# TempController.net
KiCad netlist of a schematic drawn in Altium Designer
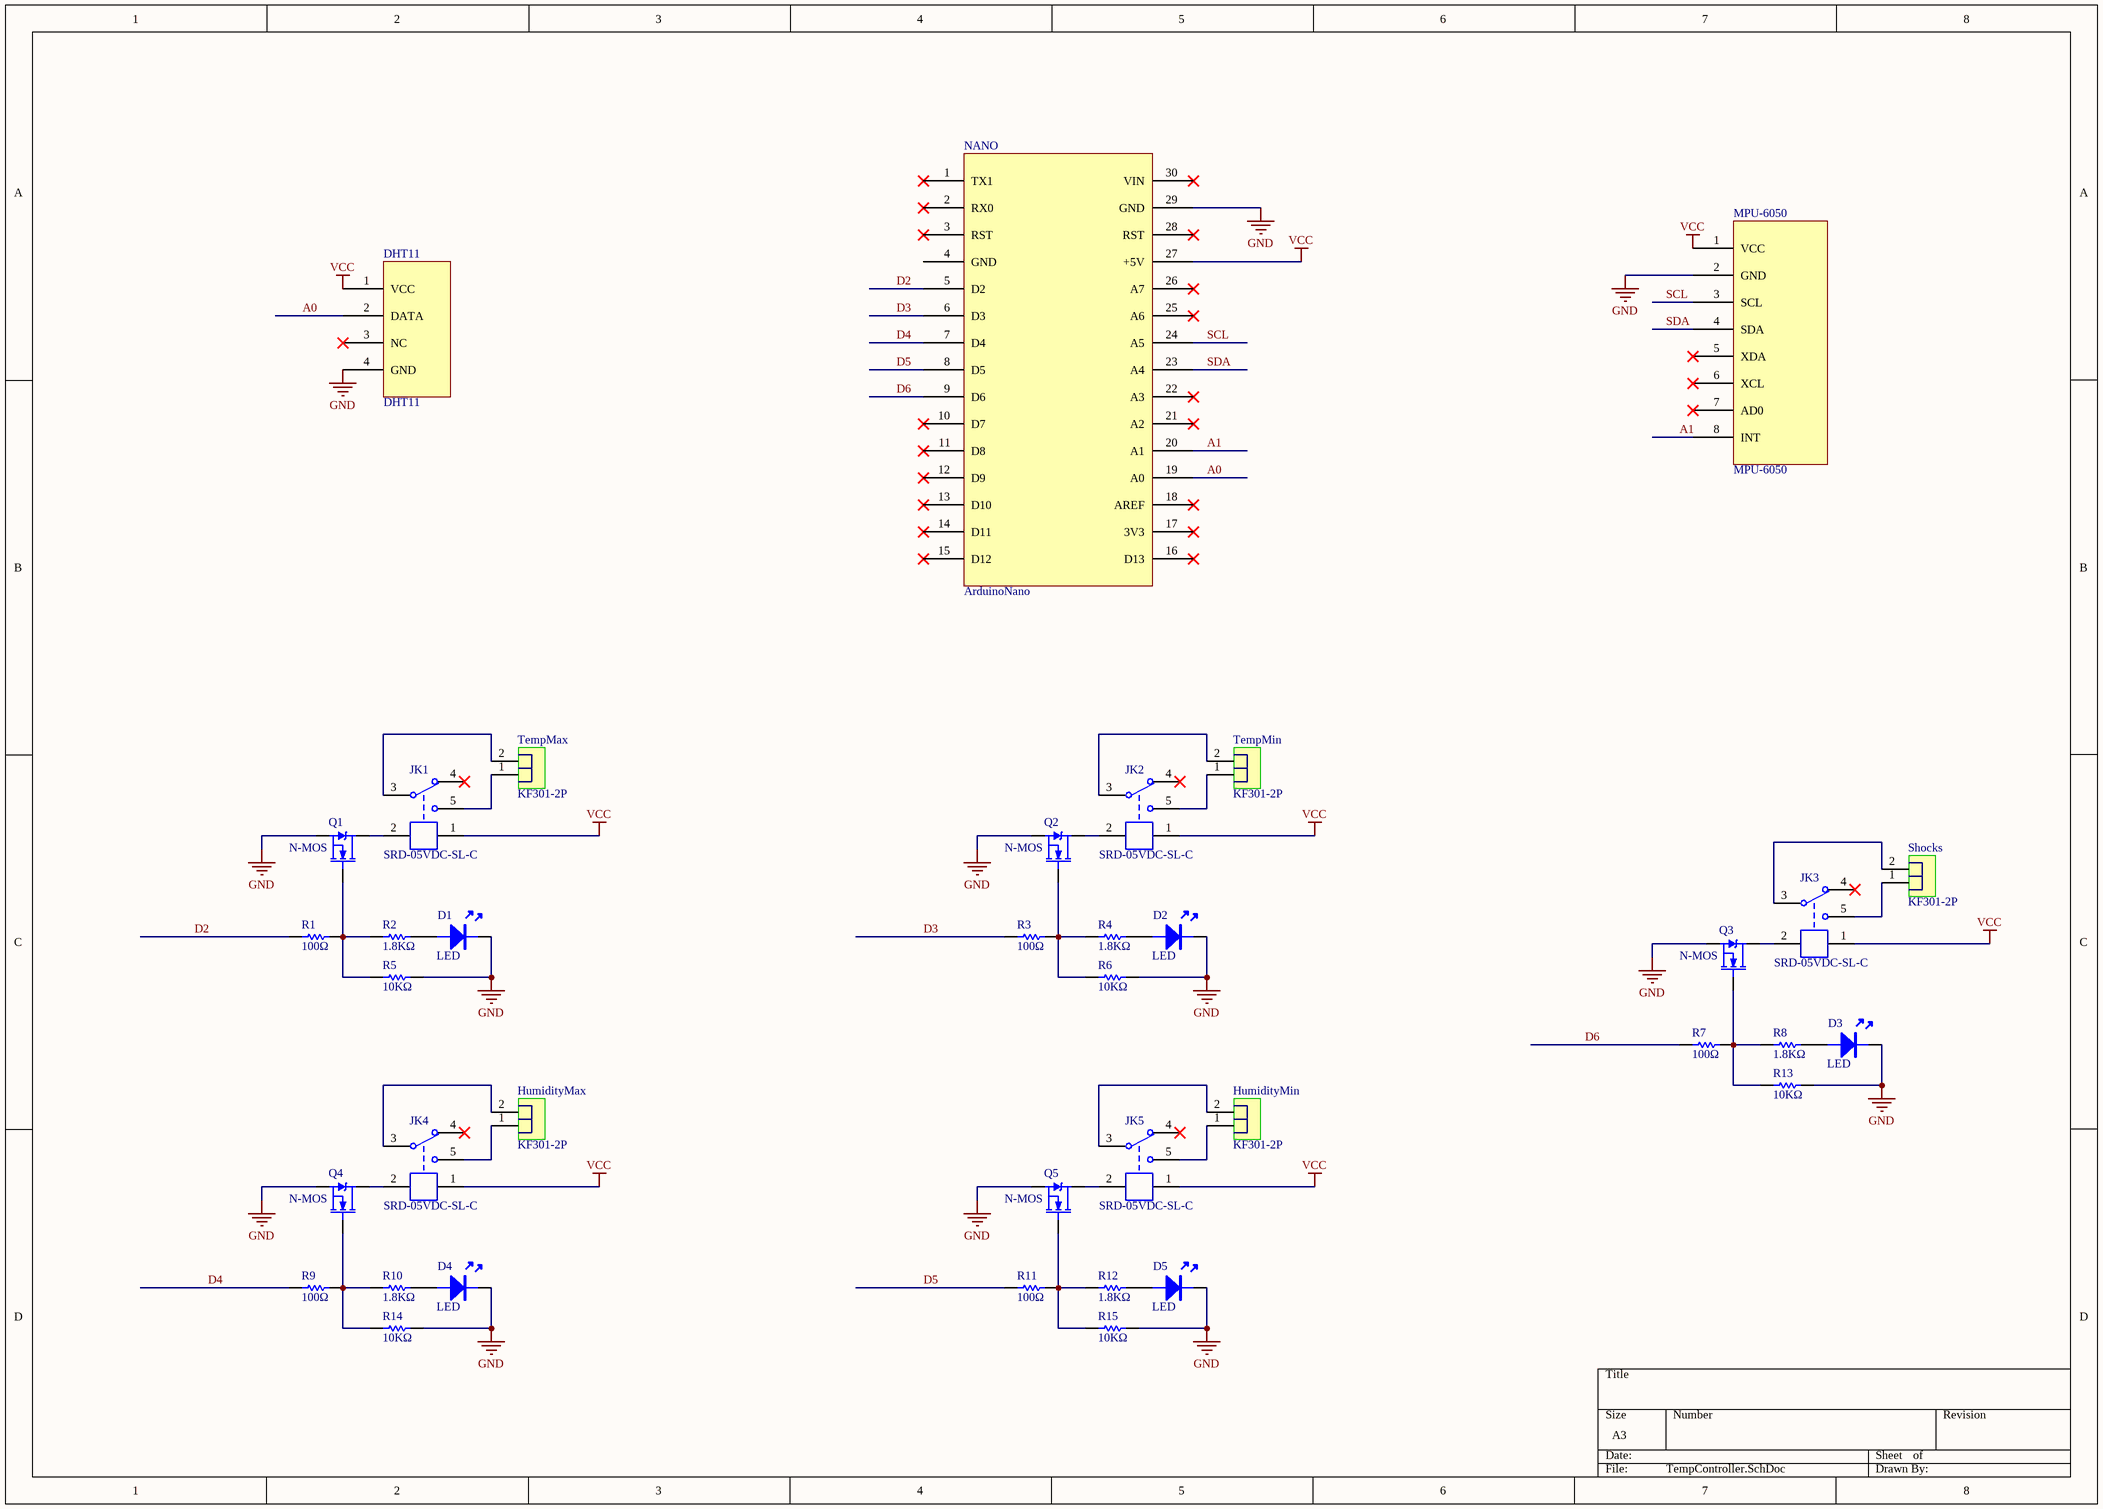
[diagram p0: TempController.SchDoc]

(export (version "E")
  (design (tool "Eeschema 10.0.6"))
  (components
    (comp (ref "D1") (value "LED") (footprint "LED-0805Y") (libsource (lib "LED") (part "LED")))
    (comp (ref "D2") (value "LED") (footprint "LED-0805Y") (libsource (lib "LED") (part "LED")))
    (comp (ref "D3") (value "LED") (footprint "LED-0805Y") (libsource (lib "LED") (part "LED")))
    (comp (ref "D4") (value "LED") (footprint "LED-0805Y") (libsource (lib "LED") (part "LED")))
    (comp (ref "D5") (value "LED") (footprint "LED-0805Y") (libsource (lib "LED") (part "LED")))
    (comp (ref "DHT11") (value "DHT11") (footprint "DHT11") (libsource (lib "TempController") (part "DHT11")))
    (comp (ref "HumidityMax")
      (value "KF301-2P")
      (footprint "KF128-3.81-2P")
      (libsource (lib "KF128") (part "KF128-2P"))
    )
    (comp (ref "HumidityMin")
      (value "KF301-2P")
      (footprint "KF128-3.81-2P")
      (libsource (lib "KF128") (part "KF128-2P"))
    )
    (comp (ref "JK1")
      (value "SRD-05VDC-SL-C")
      (footprint "SRD-C_B")
      (description "5V一组转换")
      (libsource (lib "继电器") (part "SRD-05VDC-SL-C"))
    )
    (comp (ref "JK2")
      (value "SRD-05VDC-SL-C")
      (footprint "SRD-C_B")
      (description "5V一组转换")
      (libsource (lib "继电器") (part "SRD-05VDC-SL-C"))
    )
    (comp (ref "JK3")
      (value "SRD-05VDC-SL-C")
      (footprint "SRD-C_B")
      (description "5V一组转换")
      (libsource (lib "继电器") (part "SRD-05VDC-SL-C"))
    )
    (comp (ref "JK4")
      (value "SRD-05VDC-SL-C")
      (footprint "SRD-C_B")
      (description "5V一组转换")
      (libsource (lib "继电器") (part "SRD-05VDC-SL-C"))
    )
    (comp (ref "JK5")
      (value "SRD-05VDC-SL-C")
      (footprint "SRD-C_B")
      (description "5V一组转换")
      (libsource (lib "继电器") (part "SRD-05VDC-SL-C"))
    )
    (comp (ref "MPU-6050")
      (value "MPU-6050")
      (footprint "MPU-6050")
      (libsource (lib "TempController") (part "MPU-6050"))
    )
    (comp (ref "NANO")
      (value "ArduinoNano")
      (footprint "ArduinoNano")
      (libsource (lib "TempController") (part "ArduinoNano"))
    )
    (comp (ref "Q1")
      (value "N-MOS")
      (footprint "TO252")
      (description "N沟道场效应管")
      (libsource (lib "MOS管") (part "N-MOS"))
    )
    (comp (ref "Q2")
      (value "N-MOS")
      (footprint "TO252")
      (description "N沟道场效应管")
      (libsource (lib "MOS管") (part "N-MOS"))
    )
    (comp (ref "Q3")
      (value "N-MOS")
      (footprint "TO252")
      (description "N沟道场效应管")
      (libsource (lib "MOS管") (part "N-MOS"))
    )
    (comp (ref "Q4")
      (value "N-MOS")
      (footprint "TO252")
      (description "N沟道场效应管")
      (libsource (lib "MOS管") (part "N-MOS"))
    )
    (comp (ref "Q5")
      (value "N-MOS")
      (footprint "TO252")
      (description "N沟道场效应管")
      (libsource (lib "MOS管") (part "N-MOS"))
    )
    (comp (ref "R1") (value "100Ω") (footprint "0805R") (libsource (lib "电阻") (part "RES")))
    (comp (ref "R2") (value "1.8KΩ") (footprint "0805R") (libsource (lib "电阻") (part "RES")))
    (comp (ref "R3") (value "100Ω") (footprint "0805R") (libsource (lib "电阻") (part "RES")))
    (comp (ref "R4") (value "1.8KΩ") (footprint "0805R") (libsource (lib "电阻") (part "RES")))
    (comp (ref "R5") (value "10KΩ") (footprint "0805R") (libsource (lib "电阻") (part "RES")))
    (comp (ref "R6") (value "10KΩ") (footprint "0805R") (libsource (lib "电阻") (part "RES")))
    (comp (ref "R7") (value "100Ω") (footprint "0805R") (libsource (lib "电阻") (part "RES")))
    (comp (ref "R8") (value "1.8KΩ") (footprint "0805R") (libsource (lib "电阻") (part "RES")))
    (comp (ref "R9") (value "100Ω") (footprint "0805R") (libsource (lib "电阻") (part "RES")))
    (comp (ref "R10") (value "1.8KΩ") (footprint "0805R") (libsource (lib "电阻") (part "RES")))
    (comp (ref "R11") (value "100Ω") (footprint "0805R") (libsource (lib "电阻") (part "RES")))
    (comp (ref "R12") (value "1.8KΩ") (footprint "0805R") (libsource (lib "电阻") (part "RES")))
    (comp (ref "R13") (value "10KΩ") (footprint "0805R") (libsource (lib "电阻") (part "RES")))
    (comp (ref "R14") (value "10KΩ") (footprint "0805R") (libsource (lib "电阻") (part "RES")))
    (comp (ref "R15") (value "10KΩ") (footprint "0805R") (libsource (lib "电阻") (part "RES")))
    (comp (ref "Shocks")
      (value "KF301-2P")
      (footprint "KF128-3.81-2P")
      (libsource (lib "KF128") (part "KF128-2P"))
    )
    (comp (ref "TempMax")
      (value "KF301-2P")
      (footprint "KF128-3.81-2P")
      (libsource (lib "KF128") (part "KF128-2P"))
    )
    (comp (ref "TempMin")
      (value "KF301-2P")
      (footprint "KF128-3.81-2P")
      (libsource (lib "KF128") (part "KF128-2P"))
    )
  )
  (nets
    (net (code "1") (name "/A0") (class "Default")
      (node (ref "DHT11") (pin "2") (pinfunction "DATA_2") (pintype "passive"))
      (node (ref "NANO") (pin "19") (pinfunction "A0_19") (pintype "passive"))
    )
    (net (code "2") (name "/A1") (class "Default")
      (node (ref "MPU-6050") (pin "8") (pinfunction "INT_8") (pintype "passive"))
      (node (ref "NANO") (pin "20") (pinfunction "A1_20") (pintype "passive"))
    )
    (net (code "3") (name "/D2") (class "Default")
      (node (ref "NANO") (pin "5") (pinfunction "D2_5") (pintype "passive"))
      (node (ref "R1") (pin "1") (pinfunction "1_1") (pintype "passive"))
    )
    (net (code "4") (name "/D3") (class "Default")
      (node (ref "NANO") (pin "6") (pinfunction "D3_6") (pintype "passive"))
      (node (ref "R3") (pin "1") (pinfunction "1_1") (pintype "passive"))
    )
    (net (code "5") (name "/D4") (class "Default")
      (node (ref "NANO") (pin "7") (pinfunction "D4_7") (pintype "passive"))
      (node (ref "R9") (pin "1") (pinfunction "1_1") (pintype "passive"))
    )
    (net (code "6") (name "/D5") (class "Default")
      (node (ref "NANO") (pin "8") (pinfunction "D5_8") (pintype "passive"))
      (node (ref "R11") (pin "1") (pinfunction "1_1") (pintype "passive"))
    )
    (net (code "7") (name "/D6") (class "Default")
      (node (ref "NANO") (pin "9") (pinfunction "D6_9") (pintype "passive"))
      (node (ref "R7") (pin "1") (pinfunction "1_1") (pintype "passive"))
    )
    (net (code "8") (name "/SCL") (class "Default")
      (node (ref "MPU-6050") (pin "3") (pinfunction "SCL_3") (pintype "passive"))
      (node (ref "NANO") (pin "24") (pinfunction "A5_24") (pintype "passive"))
    )
    (net (code "9") (name "/SDA") (class "Default")
      (node (ref "MPU-6050") (pin "4") (pinfunction "SDA_4") (pintype "passive"))
      (node (ref "NANO") (pin "23") (pinfunction "A4_23") (pintype "passive"))
    )
    (net (code "10") (name "GND") (class "Default")
      (node (ref "D1") (pin "K") (pinfunction "K_K") (pintype "passive"))
      (node (ref "D2") (pin "K") (pinfunction "K_K") (pintype "passive"))
      (node (ref "D3") (pin "K") (pinfunction "K_K") (pintype "passive"))
      (node (ref "D4") (pin "K") (pinfunction "K_K") (pintype "passive"))
      (node (ref "D5") (pin "K") (pinfunction "K_K") (pintype "passive"))
      (node (ref "DHT11") (pin "4") (pinfunction "GND_4") (pintype "passive"))
      (node (ref "MPU-6050") (pin "2") (pinfunction "GND_2") (pintype "passive"))
      (node (ref "NANO") (pin "29") (pinfunction "GND_29") (pintype "passive"))
      (node (ref "Q1") (pin "S") (pinfunction "S_S") (pintype "passive"))
      (node (ref "Q2") (pin "S") (pinfunction "S_S") (pintype "passive"))
      (node (ref "Q3") (pin "S") (pinfunction "S_S") (pintype "passive"))
      (node (ref "Q4") (pin "S") (pinfunction "S_S") (pintype "passive"))
      (node (ref "Q5") (pin "S") (pinfunction "S_S") (pintype "passive"))
      (node (ref "R13") (pin "2") (pinfunction "2_2") (pintype "passive"))
      (node (ref "R14") (pin "2") (pinfunction "2_2") (pintype "passive"))
      (node (ref "R15") (pin "2") (pinfunction "2_2") (pintype "passive"))
      (node (ref "R5") (pin "2") (pinfunction "2_2") (pintype "passive"))
      (node (ref "R6") (pin "2") (pinfunction "2_2") (pintype "passive"))
    )
    (net (code "11") (name "Net-(D1-PadA)") (class "Default")
      (node (ref "D1") (pin "A") (pinfunction "A_A") (pintype "passive"))
      (node (ref "R2") (pin "2") (pinfunction "2_2") (pintype "passive"))
    )
    (net (code "12") (name "Net-(D2-PadA)") (class "Default")
      (node (ref "D2") (pin "A") (pinfunction "A_A") (pintype "passive"))
      (node (ref "R4") (pin "2") (pinfunction "2_2") (pintype "passive"))
    )
    (net (code "13") (name "Net-(D3-PadA)") (class "Default")
      (node (ref "D3") (pin "A") (pinfunction "A_A") (pintype "passive"))
      (node (ref "R8") (pin "2") (pinfunction "2_2") (pintype "passive"))
    )
    (net (code "14") (name "Net-(D4-PadA)") (class "Default")
      (node (ref "D4") (pin "A") (pinfunction "A_A") (pintype "passive"))
      (node (ref "R10") (pin "2") (pinfunction "2_2") (pintype "passive"))
    )
    (net (code "15") (name "Net-(D5-PadA)") (class "Default")
      (node (ref "D5") (pin "A") (pinfunction "A_A") (pintype "passive"))
      (node (ref "R12") (pin "2") (pinfunction "2_2") (pintype "passive"))
    )
    (net (code "16") (name "Net-(HumidityMax-Pad1)") (class "Default")
      (node (ref "HumidityMax") (pin "1") (pinfunction "1_1") (pintype "passive"))
      (node (ref "JK4") (pin "5") (pinfunction "5_5") (pintype "passive"))
    )
    (net (code "17") (name "Net-(HumidityMax-Pad2)") (class "Default")
      (node (ref "HumidityMax") (pin "2") (pinfunction "2_2") (pintype "passive"))
      (node (ref "JK4") (pin "3") (pinfunction "3_3") (pintype "passive"))
    )
    (net (code "18") (name "Net-(HumidityMin-Pad1)") (class "Default")
      (node (ref "HumidityMin") (pin "1") (pinfunction "1_1") (pintype "passive"))
      (node (ref "JK5") (pin "5") (pinfunction "5_5") (pintype "passive"))
    )
    (net (code "19") (name "Net-(HumidityMin-Pad2)") (class "Default")
      (node (ref "HumidityMin") (pin "2") (pinfunction "2_2") (pintype "passive"))
      (node (ref "JK5") (pin "3") (pinfunction "3_3") (pintype "passive"))
    )
    (net (code "20") (name "Net-(JK1-Pad2)") (class "Default")
      (node (ref "JK1") (pin "2") (pinfunction "2_2") (pintype "passive"))
      (node (ref "Q1") (pin "D") (pinfunction "D_D") (pintype "passive"))
    )
    (net (code "21") (name "Net-(JK1-Pad3)") (class "Default")
      (node (ref "JK1") (pin "3") (pinfunction "3_3") (pintype "passive"))
      (node (ref "TempMax") (pin "2") (pinfunction "2_2") (pintype "passive"))
    )
    (net (code "22") (name "Net-(JK1-Pad5)") (class "Default")
      (node (ref "JK1") (pin "5") (pinfunction "5_5") (pintype "passive"))
      (node (ref "TempMax") (pin "1") (pinfunction "1_1") (pintype "passive"))
    )
    (net (code "23") (name "Net-(JK2-Pad2)") (class "Default")
      (node (ref "JK2") (pin "2") (pinfunction "2_2") (pintype "passive"))
      (node (ref "Q2") (pin "D") (pinfunction "D_D") (pintype "passive"))
    )
    (net (code "24") (name "Net-(JK2-Pad3)") (class "Default")
      (node (ref "JK2") (pin "3") (pinfunction "3_3") (pintype "passive"))
      (node (ref "TempMin") (pin "2") (pinfunction "2_2") (pintype "passive"))
    )
    (net (code "25") (name "Net-(JK2-Pad5)") (class "Default")
      (node (ref "JK2") (pin "5") (pinfunction "5_5") (pintype "passive"))
      (node (ref "TempMin") (pin "1") (pinfunction "1_1") (pintype "passive"))
    )
    (net (code "26") (name "Net-(JK3-Pad2)") (class "Default")
      (node (ref "JK3") (pin "2") (pinfunction "2_2") (pintype "passive"))
      (node (ref "Q3") (pin "D") (pinfunction "D_D") (pintype "passive"))
    )
    (net (code "27") (name "Net-(JK3-Pad3)") (class "Default")
      (node (ref "JK3") (pin "3") (pinfunction "3_3") (pintype "passive"))
      (node (ref "Shocks") (pin "2") (pinfunction "2_2") (pintype "passive"))
    )
    (net (code "28") (name "Net-(JK3-Pad5)") (class "Default")
      (node (ref "JK3") (pin "5") (pinfunction "5_5") (pintype "passive"))
      (node (ref "Shocks") (pin "1") (pinfunction "1_1") (pintype "passive"))
    )
    (net (code "29") (name "Net-(JK4-Pad2)") (class "Default")
      (node (ref "JK4") (pin "2") (pinfunction "2_2") (pintype "passive"))
      (node (ref "Q4") (pin "D") (pinfunction "D_D") (pintype "passive"))
    )
    (net (code "30") (name "Net-(JK5-Pad2)") (class "Default")
      (node (ref "JK5") (pin "2") (pinfunction "2_2") (pintype "passive"))
      (node (ref "Q5") (pin "D") (pinfunction "D_D") (pintype "passive"))
    )
    (net (code "31") (name "Net-(Q1-PadG)") (class "Default")
      (node (ref "Q1") (pin "G") (pinfunction "G_G") (pintype "passive"))
      (node (ref "R1") (pin "2") (pinfunction "2_2") (pintype "passive"))
      (node (ref "R2") (pin "1") (pinfunction "1_1") (pintype "passive"))
      (node (ref "R5") (pin "1") (pinfunction "1_1") (pintype "passive"))
    )
    (net (code "32") (name "Net-(Q2-PadG)") (class "Default")
      (node (ref "Q2") (pin "G") (pinfunction "G_G") (pintype "passive"))
      (node (ref "R3") (pin "2") (pinfunction "2_2") (pintype "passive"))
      (node (ref "R4") (pin "1") (pinfunction "1_1") (pintype "passive"))
      (node (ref "R6") (pin "1") (pinfunction "1_1") (pintype "passive"))
    )
    (net (code "33") (name "Net-(Q3-PadG)") (class "Default")
      (node (ref "Q3") (pin "G") (pinfunction "G_G") (pintype "passive"))
      (node (ref "R13") (pin "1") (pinfunction "1_1") (pintype "passive"))
      (node (ref "R7") (pin "2") (pinfunction "2_2") (pintype "passive"))
      (node (ref "R8") (pin "1") (pinfunction "1_1") (pintype "passive"))
    )
    (net (code "34") (name "Net-(Q4-PadG)") (class "Default")
      (node (ref "Q4") (pin "G") (pinfunction "G_G") (pintype "passive"))
      (node (ref "R10") (pin "1") (pinfunction "1_1") (pintype "passive"))
      (node (ref "R14") (pin "1") (pinfunction "1_1") (pintype "passive"))
      (node (ref "R9") (pin "2") (pinfunction "2_2") (pintype "passive"))
    )
    (net (code "35") (name "Net-(Q5-PadG)") (class "Default")
      (node (ref "Q5") (pin "G") (pinfunction "G_G") (pintype "passive"))
      (node (ref "R11") (pin "2") (pinfunction "2_2") (pintype "passive"))
      (node (ref "R12") (pin "1") (pinfunction "1_1") (pintype "passive"))
      (node (ref "R15") (pin "1") (pinfunction "1_1") (pintype "passive"))
    )
    (net (code "36") (name "VCC") (class "Default")
      (node (ref "DHT11") (pin "1") (pinfunction "VCC_1") (pintype "passive"))
      (node (ref "JK1") (pin "1") (pinfunction "1_1") (pintype "passive"))
      (node (ref "JK2") (pin "1") (pinfunction "1_1") (pintype "passive"))
      (node (ref "JK3") (pin "1") (pinfunction "1_1") (pintype "passive"))
      (node (ref "JK4") (pin "1") (pinfunction "1_1") (pintype "passive"))
      (node (ref "JK5") (pin "1") (pinfunction "1_1") (pintype "passive"))
      (node (ref "MPU-6050") (pin "1") (pinfunction "VCC_1") (pintype "passive"))
      (node (ref "NANO") (pin "27") (pinfunction "+5V_27") (pintype "passive"))
    )
    (net (code "37") (name "unconnected-(DHT11-NC-Pad3)") (class "Default")
      (node (ref "DHT11") (pin "3") (pinfunction "NC_3") (pintype "passive+no_connect"))
    )
    (net (code "38") (name "unconnected-(JK1-Pad4)") (class "Default")
      (node (ref "JK1") (pin "4") (pinfunction "4_4") (pintype "passive+no_connect"))
    )
    (net (code "39") (name "unconnected-(JK2-Pad4)") (class "Default")
      (node (ref "JK2") (pin "4") (pinfunction "4_4") (pintype "passive+no_connect"))
    )
    (net (code "40") (name "unconnected-(JK3-Pad4)") (class "Default")
      (node (ref "JK3") (pin "4") (pinfunction "4_4") (pintype "passive+no_connect"))
    )
    (net (code "41") (name "unconnected-(JK4-Pad4)") (class "Default")
      (node (ref "JK4") (pin "4") (pinfunction "4_4") (pintype "passive+no_connect"))
    )
    (net (code "42") (name "unconnected-(JK5-Pad4)") (class "Default")
      (node (ref "JK5") (pin "4") (pinfunction "4_4") (pintype "passive+no_connect"))
    )
    (net (code "43") (name "unconnected-(MPU-6050-AD0-Pad7)") (class "Default")
      (node (ref "MPU-6050") (pin "7") (pinfunction "AD0_7") (pintype "passive+no_connect"))
    )
    (net (code "44") (name "unconnected-(MPU-6050-XCL-Pad6)") (class "Default")
      (node (ref "MPU-6050") (pin "6") (pinfunction "XCL_6") (pintype "passive+no_connect"))
    )
    (net (code "45") (name "unconnected-(MPU-6050-XDA-Pad5)") (class "Default")
      (node (ref "MPU-6050") (pin "5") (pinfunction "XDA_5") (pintype "passive+no_connect"))
    )
    (net (code "46") (name "unconnected-(NANO-3V3-Pad17)") (class "Default")
      (node (ref "NANO") (pin "17") (pinfunction "3V3_17") (pintype "passive+no_connect"))
    )
    (net (code "47") (name "unconnected-(NANO-A2-Pad21)") (class "Default")
      (node (ref "NANO") (pin "21") (pinfunction "A2_21") (pintype "passive+no_connect"))
    )
    (net (code "48") (name "unconnected-(NANO-A3-Pad22)") (class "Default")
      (node (ref "NANO") (pin "22") (pinfunction "A3_22") (pintype "passive+no_connect"))
    )
    (net (code "49") (name "unconnected-(NANO-A6-Pad25)") (class "Default")
      (node (ref "NANO") (pin "25") (pinfunction "A6_25") (pintype "passive+no_connect"))
    )
    (net (code "50") (name "unconnected-(NANO-A7-Pad26)") (class "Default")
      (node (ref "NANO") (pin "26") (pinfunction "A7_26") (pintype "passive+no_connect"))
    )
    (net (code "51") (name "unconnected-(NANO-AREF-Pad18)") (class "Default")
      (node (ref "NANO") (pin "18") (pinfunction "AREF_18") (pintype "passive+no_connect"))
    )
    (net (code "52") (name "unconnected-(NANO-D7-Pad10)") (class "Default")
      (node (ref "NANO") (pin "10") (pinfunction "D7_10") (pintype "passive+no_connect"))
    )
    (net (code "53") (name "unconnected-(NANO-D8-Pad11)") (class "Default")
      (node (ref "NANO") (pin "11") (pinfunction "D8_11") (pintype "passive+no_connect"))
    )
    (net (code "54") (name "unconnected-(NANO-D9-Pad12)") (class "Default")
      (node (ref "NANO") (pin "12") (pinfunction "D9_12") (pintype "passive+no_connect"))
    )
    (net (code "55") (name "unconnected-(NANO-D10-Pad13)") (class "Default")
      (node (ref "NANO") (pin "13") (pinfunction "D10_13") (pintype "passive+no_connect"))
    )
    (net (code "56") (name "unconnected-(NANO-D11-Pad14)") (class "Default")
      (node (ref "NANO") (pin "14") (pinfunction "D11_14") (pintype "passive+no_connect"))
    )
    (net (code "57") (name "unconnected-(NANO-D12-Pad15)") (class "Default")
      (node (ref "NANO") (pin "15") (pinfunction "D12_15") (pintype "passive+no_connect"))
    )
    (net (code "58") (name "unconnected-(NANO-D13-Pad16)") (class "Default")
      (node (ref "NANO") (pin "16") (pinfunction "D13_16") (pintype "passive+no_connect"))
    )
    (net (code "59") (name "unconnected-(NANO-GND-Pad4)") (class "Default")
      (node (ref "NANO") (pin "4") (pinfunction "GND_4") (pintype "passive"))
    )
    (net (code "60") (name "unconnected-(NANO-RST-Pad3)") (class "Default")
      (node (ref "NANO") (pin "3") (pinfunction "RST_3") (pintype "passive+no_connect"))
    )
    (net (code "61") (name "unconnected-(NANO-RST-Pad28)") (class "Default")
      (node (ref "NANO") (pin "28") (pinfunction "RST_28") (pintype "passive+no_connect"))
    )
    (net (code "62") (name "unconnected-(NANO-RX0-Pad2)") (class "Default")
      (node (ref "NANO") (pin "2") (pinfunction "RX0_2") (pintype "passive+no_connect"))
    )
    (net (code "63") (name "unconnected-(NANO-TX1-Pad1)") (class "Default")
      (node (ref "NANO") (pin "1") (pinfunction "TX1_1") (pintype "passive+no_connect"))
    )
    (net (code "64") (name "unconnected-(NANO-VIN-Pad30)") (class "Default")
      (node (ref "NANO") (pin "30") (pinfunction "VIN_30") (pintype "passive+no_connect"))
    )
  )
)
